# TSOP_to_DIP_adapter.net
KiCad netlist of a schematic drawn in EAGLE
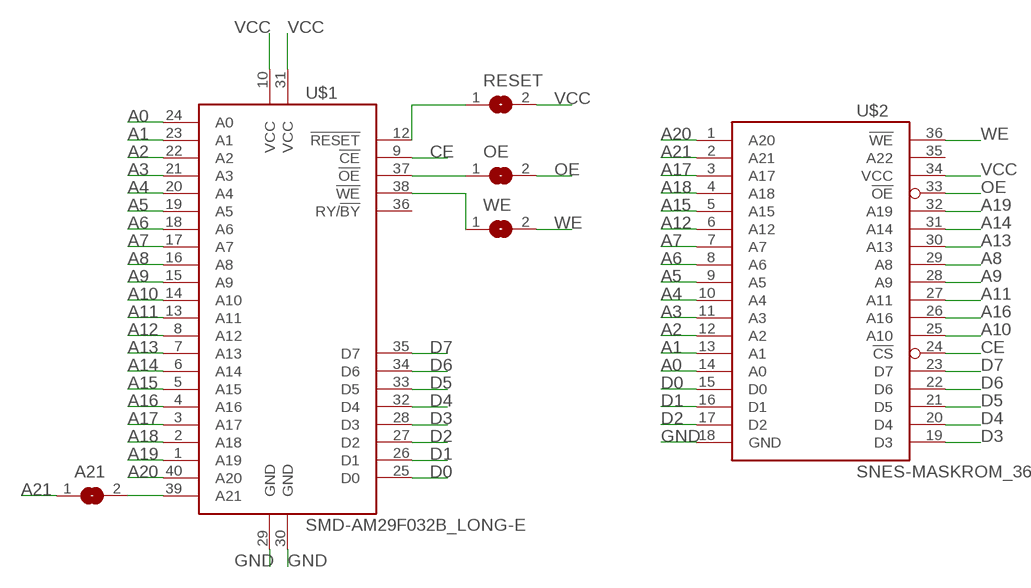
[diagram p0: schematic, sheet 1]

(export (version "E")
  (design (tool "Eeschema 10.0.6"))
  (components
    (comp (ref "A21")
      (value "SMD-SOLDER_JUMPER_2")
      (footprint "eagle-import:SJ")
      (libsource (lib "eagle-import") (part "SMD-SOLDER_JUMPER_2"))
    )
    (comp (ref "OE")
      (value "SMD-SOLDER_JUMPER_2")
      (footprint "eagle-import:SJ")
      (libsource (lib "eagle-import") (part "SMD-SOLDER_JUMPER_2"))
    )
    (comp (ref "RESET")
      (value "SMD-SOLDER_JUMPER_2")
      (footprint "eagle-import:SJ")
      (libsource (lib "eagle-import") (part "SMD-SOLDER_JUMPER_2"))
    )
    (comp (ref "U$1")
      (value "SMD-AM29F032B_LONG-E")
      (footprint "eagle-import:40-TSOP_LONG")
      (libsource (lib "eagle-import") (part "SMD-AM29F032B_LONG-E"))
    )
    (comp (ref "U$2")
      (value "SNES-MASKROM_36")
      (footprint "eagle-import:36-PDIP")
      (libsource (lib "eagle-import") (part "SNES-MASKROM_36"))
    )
    (comp (ref "WE")
      (value "SMD-SOLDER_JUMPER_2")
      (footprint "eagle-import:SJ")
      (libsource (lib "eagle-import") (part "SMD-SOLDER_JUMPER_2"))
    )
  )
  (nets
    (net (code "1") (name "/A0") (class "Default")
      (node (ref "U$1") (pin "24") (pinfunction "A0_24") (pintype "input"))
      (node (ref "U$2") (pin "14") (pinfunction "A0_14") (pintype "input"))
    )
    (net (code "2") (name "/A1") (class "Default")
      (node (ref "U$1") (pin "23") (pinfunction "A1_23") (pintype "input"))
      (node (ref "U$2") (pin "13") (pinfunction "A1_13") (pintype "input"))
    )
    (net (code "3") (name "/A2") (class "Default")
      (node (ref "U$1") (pin "22") (pinfunction "A2_22") (pintype "input"))
      (node (ref "U$2") (pin "12") (pinfunction "A2_12") (pintype "input"))
    )
    (net (code "4") (name "/A3") (class "Default")
      (node (ref "U$1") (pin "21") (pinfunction "A3_21") (pintype "input"))
      (node (ref "U$2") (pin "11") (pinfunction "A3_11") (pintype "input"))
    )
    (net (code "5") (name "/A4") (class "Default")
      (node (ref "U$1") (pin "20") (pinfunction "A4_20") (pintype "input"))
      (node (ref "U$2") (pin "10") (pinfunction "A4_10") (pintype "input"))
    )
    (net (code "6") (name "/A5") (class "Default")
      (node (ref "U$1") (pin "19") (pinfunction "A5_19") (pintype "input"))
      (node (ref "U$2") (pin "9") (pinfunction "A5_9") (pintype "input"))
    )
    (net (code "7") (name "/A6") (class "Default")
      (node (ref "U$1") (pin "18") (pinfunction "A6_18") (pintype "input"))
      (node (ref "U$2") (pin "8") (pinfunction "A6_8") (pintype "input"))
    )
    (net (code "8") (name "/A7") (class "Default")
      (node (ref "U$1") (pin "17") (pinfunction "A7_17") (pintype "input"))
      (node (ref "U$2") (pin "7") (pinfunction "A7_7") (pintype "input"))
    )
    (net (code "9") (name "/A8") (class "Default")
      (node (ref "U$1") (pin "16") (pinfunction "A8_16") (pintype "input"))
      (node (ref "U$2") (pin "29") (pinfunction "A8_29") (pintype "input"))
    )
    (net (code "10") (name "/A9") (class "Default")
      (node (ref "U$1") (pin "15") (pinfunction "A9_15") (pintype "input"))
      (node (ref "U$2") (pin "28") (pinfunction "A9_28") (pintype "input"))
    )
    (net (code "11") (name "/A10") (class "Default")
      (node (ref "U$1") (pin "14") (pinfunction "A10_14") (pintype "input"))
      (node (ref "U$2") (pin "25") (pinfunction "A10_25") (pintype "input"))
    )
    (net (code "12") (name "/A11") (class "Default")
      (node (ref "U$1") (pin "13") (pinfunction "A11_13") (pintype "input"))
      (node (ref "U$2") (pin "27") (pinfunction "A11_27") (pintype "input"))
    )
    (net (code "13") (name "/A12") (class "Default")
      (node (ref "U$1") (pin "8") (pinfunction "A12_8") (pintype "input"))
      (node (ref "U$2") (pin "6") (pinfunction "A12_6") (pintype "input"))
    )
    (net (code "14") (name "/A13") (class "Default")
      (node (ref "U$1") (pin "7") (pinfunction "A13_7") (pintype "input"))
      (node (ref "U$2") (pin "30") (pinfunction "A13_30") (pintype "input"))
    )
    (net (code "15") (name "/A14") (class "Default")
      (node (ref "U$1") (pin "6") (pinfunction "A14_6") (pintype "input"))
      (node (ref "U$2") (pin "31") (pinfunction "A14_31") (pintype "input"))
    )
    (net (code "16") (name "/A15") (class "Default")
      (node (ref "U$1") (pin "5") (pinfunction "A15_5") (pintype "input"))
      (node (ref "U$2") (pin "5") (pinfunction "A15_5") (pintype "input"))
    )
    (net (code "17") (name "/A16") (class "Default")
      (node (ref "U$1") (pin "4") (pinfunction "A16_4") (pintype "input"))
      (node (ref "U$2") (pin "26") (pinfunction "A16_26") (pintype "input"))
    )
    (net (code "18") (name "/A17") (class "Default")
      (node (ref "U$1") (pin "3") (pinfunction "A17_3") (pintype "input"))
      (node (ref "U$2") (pin "3") (pinfunction "A17_3") (pintype "input"))
    )
    (net (code "19") (name "/A18") (class "Default")
      (node (ref "U$1") (pin "2") (pinfunction "A18_2") (pintype "input"))
      (node (ref "U$2") (pin "4") (pinfunction "A18_4") (pintype "input"))
    )
    (net (code "20") (name "/A19") (class "Default")
      (node (ref "U$1") (pin "1") (pinfunction "A19_1") (pintype "input"))
      (node (ref "U$2") (pin "32") (pinfunction "A19_32") (pintype "input"))
    )
    (net (code "21") (name "/A20") (class "Default")
      (node (ref "U$1") (pin "40") (pinfunction "A20_40") (pintype "input"))
      (node (ref "U$2") (pin "1") (pinfunction "A20_1") (pintype "input"))
    )
    (net (code "22") (name "/A21") (class "Default")
      (node (ref "A21") (pin "1") (pinfunction "1_1") (pintype "passive"))
      (node (ref "U$2") (pin "2") (pinfunction "A21_2") (pintype "input"))
    )
    (net (code "23") (name "/CE") (class "Default")
      (node (ref "U$1") (pin "9") (pinfunction "~{CE}_9") (pintype "input"))
      (node (ref "U$2") (pin "24") (pinfunction "~{CS}_24") (pintype "input"))
    )
    (net (code "24") (name "/D0") (class "Default")
      (node (ref "U$1") (pin "25") (pinfunction "D0_25") (pintype "bidirectional"))
      (node (ref "U$2") (pin "15") (pinfunction "D0_15") (pintype "output"))
    )
    (net (code "25") (name "/D1") (class "Default")
      (node (ref "U$1") (pin "26") (pinfunction "D1_26") (pintype "bidirectional"))
      (node (ref "U$2") (pin "16") (pinfunction "D1_16") (pintype "output"))
    )
    (net (code "26") (name "/D2") (class "Default")
      (node (ref "U$1") (pin "27") (pinfunction "D2_27") (pintype "bidirectional"))
      (node (ref "U$2") (pin "17") (pinfunction "D2_17") (pintype "output"))
    )
    (net (code "27") (name "/D3") (class "Default")
      (node (ref "U$1") (pin "28") (pinfunction "D3_28") (pintype "bidirectional"))
      (node (ref "U$2") (pin "19") (pinfunction "D3_19") (pintype "output"))
    )
    (net (code "28") (name "/D4") (class "Default")
      (node (ref "U$1") (pin "32") (pinfunction "D4_32") (pintype "bidirectional"))
      (node (ref "U$2") (pin "20") (pinfunction "D4_20") (pintype "output"))
    )
    (net (code "29") (name "/D5") (class "Default")
      (node (ref "U$1") (pin "33") (pinfunction "D5_33") (pintype "bidirectional"))
      (node (ref "U$2") (pin "21") (pinfunction "D5_21") (pintype "output"))
    )
    (net (code "30") (name "/D6") (class "Default")
      (node (ref "U$1") (pin "34") (pinfunction "D6_34") (pintype "bidirectional"))
      (node (ref "U$2") (pin "22") (pinfunction "D6_22") (pintype "output"))
    )
    (net (code "31") (name "/D7") (class "Default")
      (node (ref "U$1") (pin "35") (pinfunction "D7_35") (pintype "bidirectional"))
      (node (ref "U$2") (pin "23") (pinfunction "D7_23") (pintype "output"))
    )
    (net (code "32") (name "/GND") (class "Default")
      (node (ref "U$1") (pin "29") (pinfunction "GND_29") (pintype "power_in"))
      (node (ref "U$1") (pin "30") (pinfunction "GND_30") (pintype "power_in"))
      (node (ref "U$2") (pin "18") (pinfunction "GND_18") (pintype "power_in"))
    )
    (net (code "33") (name "/OE") (class "Default")
      (node (ref "OE") (pin "2") (pinfunction "2_2") (pintype "passive"))
      (node (ref "U$2") (pin "33") (pinfunction "~{OE}_33") (pintype "input"))
    )
    (net (code "34") (name "/VCC") (class "Default")
      (node (ref "RESET") (pin "2") (pinfunction "2_2") (pintype "passive"))
      (node (ref "U$1") (pin "10") (pinfunction "VCC_10") (pintype "power_in"))
      (node (ref "U$1") (pin "31") (pinfunction "VCC_31") (pintype "power_in"))
      (node (ref "U$2") (pin "34") (pinfunction "VCC_34") (pintype "power_in"))
    )
    (net (code "35") (name "/WE") (class "Default")
      (node (ref "U$2") (pin "36") (pinfunction "~{WE}_36") (pintype "input"))
      (node (ref "WE") (pin "2") (pinfunction "2_2") (pintype "passive"))
    )
    (net (code "36") (name "Net-(U$1-A21)") (class "Default")
      (node (ref "A21") (pin "2") (pinfunction "2_2") (pintype "passive"))
      (node (ref "U$1") (pin "39") (pinfunction "A21_39") (pintype "input"))
    )
    (net (code "37") (name "Net-(U$1-~{OE})") (class "Default")
      (node (ref "OE") (pin "1") (pinfunction "1_1") (pintype "passive"))
      (node (ref "U$1") (pin "37") (pinfunction "~{OE}_37") (pintype "input"))
    )
    (net (code "38") (name "Net-(U$1-~{RESET})") (class "Default")
      (node (ref "RESET") (pin "1") (pinfunction "1_1") (pintype "passive"))
      (node (ref "U$1") (pin "12") (pinfunction "~{RESET}_12") (pintype "input"))
    )
    (net (code "39") (name "Net-(U$1-~{WE})") (class "Default")
      (node (ref "U$1") (pin "38") (pinfunction "~{WE}_38") (pintype "input"))
      (node (ref "WE") (pin "1") (pinfunction "1_1") (pintype "passive"))
    )
    (net (code "40") (name "unconnected-(U$1-RY{slash}~{BY}-Pad36)") (class "Default")
      (node (ref "U$1") (pin "36") (pinfunction "RY/~{BY}_36") (pintype "output"))
    )
    (net (code "41") (name "unconnected-(U$2-A22-Pad35)") (class "Default")
      (node (ref "U$2") (pin "35") (pinfunction "A22_35") (pintype "input"))
    )
  )
)
